# GotEm.net
KiCad netlist of a schematic drawn in Altium Designer
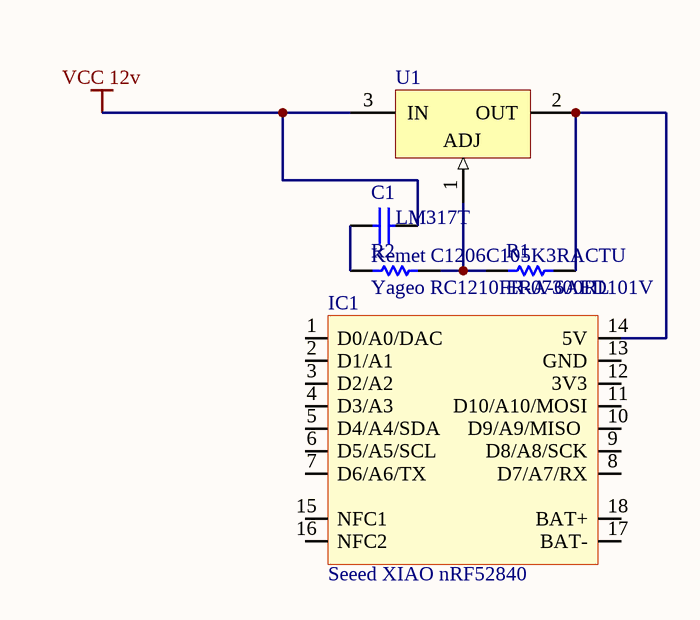
[diagram p0: GotEm.SchDoc]

(export (version "E")
  (design (tool "Eeschema 10.0.6"))
  (components
    (comp (ref "C1")
      (value "Kemet C1206C105K3RACTU")
      (footprint "CAPC3216X14N")
      (description "Capacitor; Ceramic; Cap; 1.00uF; Tol 10%; SMT; Vol-Rtg 25V; High Cap; X7R; Tape And R")
      (fields (field (name "MANUFACTURER PART NUMBER") "C1206C105K3RACTU"))
      (libsource (lib "My Personal Space") (part "SYM-9109580191654ece-1"))
    )
    (comp (ref "IC1")
      (value "Seeed XIAO nRF52840")
      (footprint "Seeed Studio 102010328-Footprint-1")
      (fields
        (field (name "MANUFACTURER PART NUMBER") "102010448")
        (field (name "MANUFACTURER") "Seeed Studio")
      )
      (libsource (lib "My Personal Space") (part "SYM-92e65d880fcb4d21-1"))
    )
    (comp (ref "R1")
      (value "ERA-6AED101V")
      (footprint "PCB-tzssradp8ccpgaiuqbqn-1")
      (description "Res Thin Film 0805 100 Ohm 0.5% 1/8W Â±25ppm/Â°C Molded SMD SMD Punched Carrier T/R")
      (libsource (lib "My Personal Space") (part "SYM-01e0cab5be89de27-1"))
    )
    (comp (ref "R2")
      (value "Yageo RC1210FR-07300RL")
      (footprint "RESC3126X60X50LL10T20")
      (description "Thick Film Resistors - SMD 300 OHM 1%")
      (fields (field (name "MANUFACTURER PART NUMBER") "RC1210FR-07300RL"))
      (libsource (lib "My Personal Space") (part "RES-2"))
    )
    (comp (ref "U1")
      (value "LM317T")
      (footprint "TO-220")
      (description "Adjustable Positive Standard Regulator, 1.2V Min, 37V Max, BIPolar, PSFM3")
      (libsource (lib "My Personal Space") (part "PM-REG-117-SIL3"))
    )
  )
  (nets
    (net (code "1") (name "Net-(C1-Pad1)") (class "Default")
      (node (ref "C1") (pin "1") (pinfunction "1_1") (pintype "passive"))
      (node (ref "R2") (pin "1") (pinfunction "1_1") (pintype "passive"))
    )
    (net (code "2") (name "Net-(IC1-5V)") (class "Default")
      (node (ref "IC1") (pin "14") (pinfunction "5V_14") (pintype "passive"))
      (node (ref "R1") (pin "2") (pinfunction "2_2") (pintype "passive"))
      (node (ref "U1") (pin "2") (pinfunction "OUT_2") (pintype "power_in"))
    )
    (net (code "3") (name "Net-(U1-ADJ)") (class "Default")
      (node (ref "R1") (pin "1") (pinfunction "1_1") (pintype "passive"))
      (node (ref "R2") (pin "2") (pinfunction "2_2") (pintype "passive"))
      (node (ref "U1") (pin "1") (pinfunction "ADJ_1") (pintype "input"))
    )
    (net (code "4") (name "VCC 12v") (class "Default")
      (node (ref "C1") (pin "2") (pinfunction "2_2") (pintype "passive"))
      (node (ref "U1") (pin "3") (pinfunction "IN_3") (pintype "power_in"))
    )
    (net (code "5") (name "unconnected-(IC1-3V3-Pad12)") (class "Default")
      (node (ref "IC1") (pin "12") (pinfunction "3V3_12") (pintype "passive"))
    )
    (net (code "6") (name "unconnected-(IC1-BAT+-Pad18)") (class "Default")
      (node (ref "IC1") (pin "18") (pinfunction "BAT+_18") (pintype "passive"))
    )
    (net (code "7") (name "unconnected-(IC1-BAT--Pad17)") (class "Default")
      (node (ref "IC1") (pin "17") (pinfunction "BAT-_17") (pintype "passive"))
    )
    (net (code "8") (name "unconnected-(IC1-D0{slash}A0{slash}DAC-Pad1)") (class "Default")
      (node (ref "IC1") (pin "1") (pinfunction "D0/A0/DAC_1") (pintype "passive"))
    )
    (net (code "9") (name "unconnected-(IC1-D1{slash}A1-Pad2)") (class "Default")
      (node (ref "IC1") (pin "2") (pinfunction "D1/A1_2") (pintype "passive"))
    )
    (net (code "10") (name "unconnected-(IC1-D2{slash}A2-Pad3)") (class "Default")
      (node (ref "IC1") (pin "3") (pinfunction "D2/A2_3") (pintype "passive"))
    )
    (net (code "11") (name "unconnected-(IC1-D3{slash}A3-Pad4)") (class "Default")
      (node (ref "IC1") (pin "4") (pinfunction "D3/A3_4") (pintype "passive"))
    )
    (net (code "12") (name "unconnected-(IC1-D4{slash}A4{slash}SDA-Pad5)") (class "Default")
      (node (ref "IC1") (pin "5") (pinfunction "D4/A4/SDA_5") (pintype "passive"))
    )
    (net (code "13") (name "unconnected-(IC1-D5{slash}A5{slash}SCL-Pad6)") (class "Default")
      (node (ref "IC1") (pin "6") (pinfunction "D5/A5/SCL_6") (pintype "passive"))
    )
    (net (code "14") (name "unconnected-(IC1-D6{slash}A6{slash}TX-Pad7)") (class "Default")
      (node (ref "IC1") (pin "7") (pinfunction "D6/A6/TX_7") (pintype "passive"))
    )
    (net (code "15") (name "unconnected-(IC1-D7{slash}A7{slash}RX-Pad8)") (class "Default")
      (node (ref "IC1") (pin "8") (pinfunction "D7/A7/RX_8") (pintype "passive"))
    )
    (net (code "16") (name "unconnected-(IC1-D8{slash}A8{slash}SCK-Pad9)") (class "Default")
      (node (ref "IC1") (pin "9") (pinfunction "D8/A8/SCK_9") (pintype "passive"))
    )
    (net (code "17") (name "unconnected-(IC1-D9{slash}A9{slash}MISO-Pad10)") (class "Default")
      (node (ref "IC1") (pin "10") (pinfunction "D9/A9/MISO_10") (pintype "passive"))
    )
    (net (code "18") (name "unconnected-(IC1-D10{slash}A10{slash}MOSI-Pad11)") (class "Default")
      (node (ref "IC1") (pin "11") (pinfunction "D10/A10/MOSI_11") (pintype "passive"))
    )
    (net (code "19") (name "unconnected-(IC1-GND-Pad13)") (class "Default")
      (node (ref "IC1") (pin "13") (pinfunction "GND_13") (pintype "passive"))
    )
    (net (code "20") (name "unconnected-(IC1-NFC1-Pad15)") (class "Default")
      (node (ref "IC1") (pin "15") (pinfunction "NFC1_15") (pintype "passive"))
    )
    (net (code "21") (name "unconnected-(IC1-NFC2-Pad16)") (class "Default")
      (node (ref "IC1") (pin "16") (pinfunction "NFC2_16") (pintype "passive"))
    )
  )
)
